# Cannon_V2.net
KiCad netlist of a schematic drawn in Altium Designer
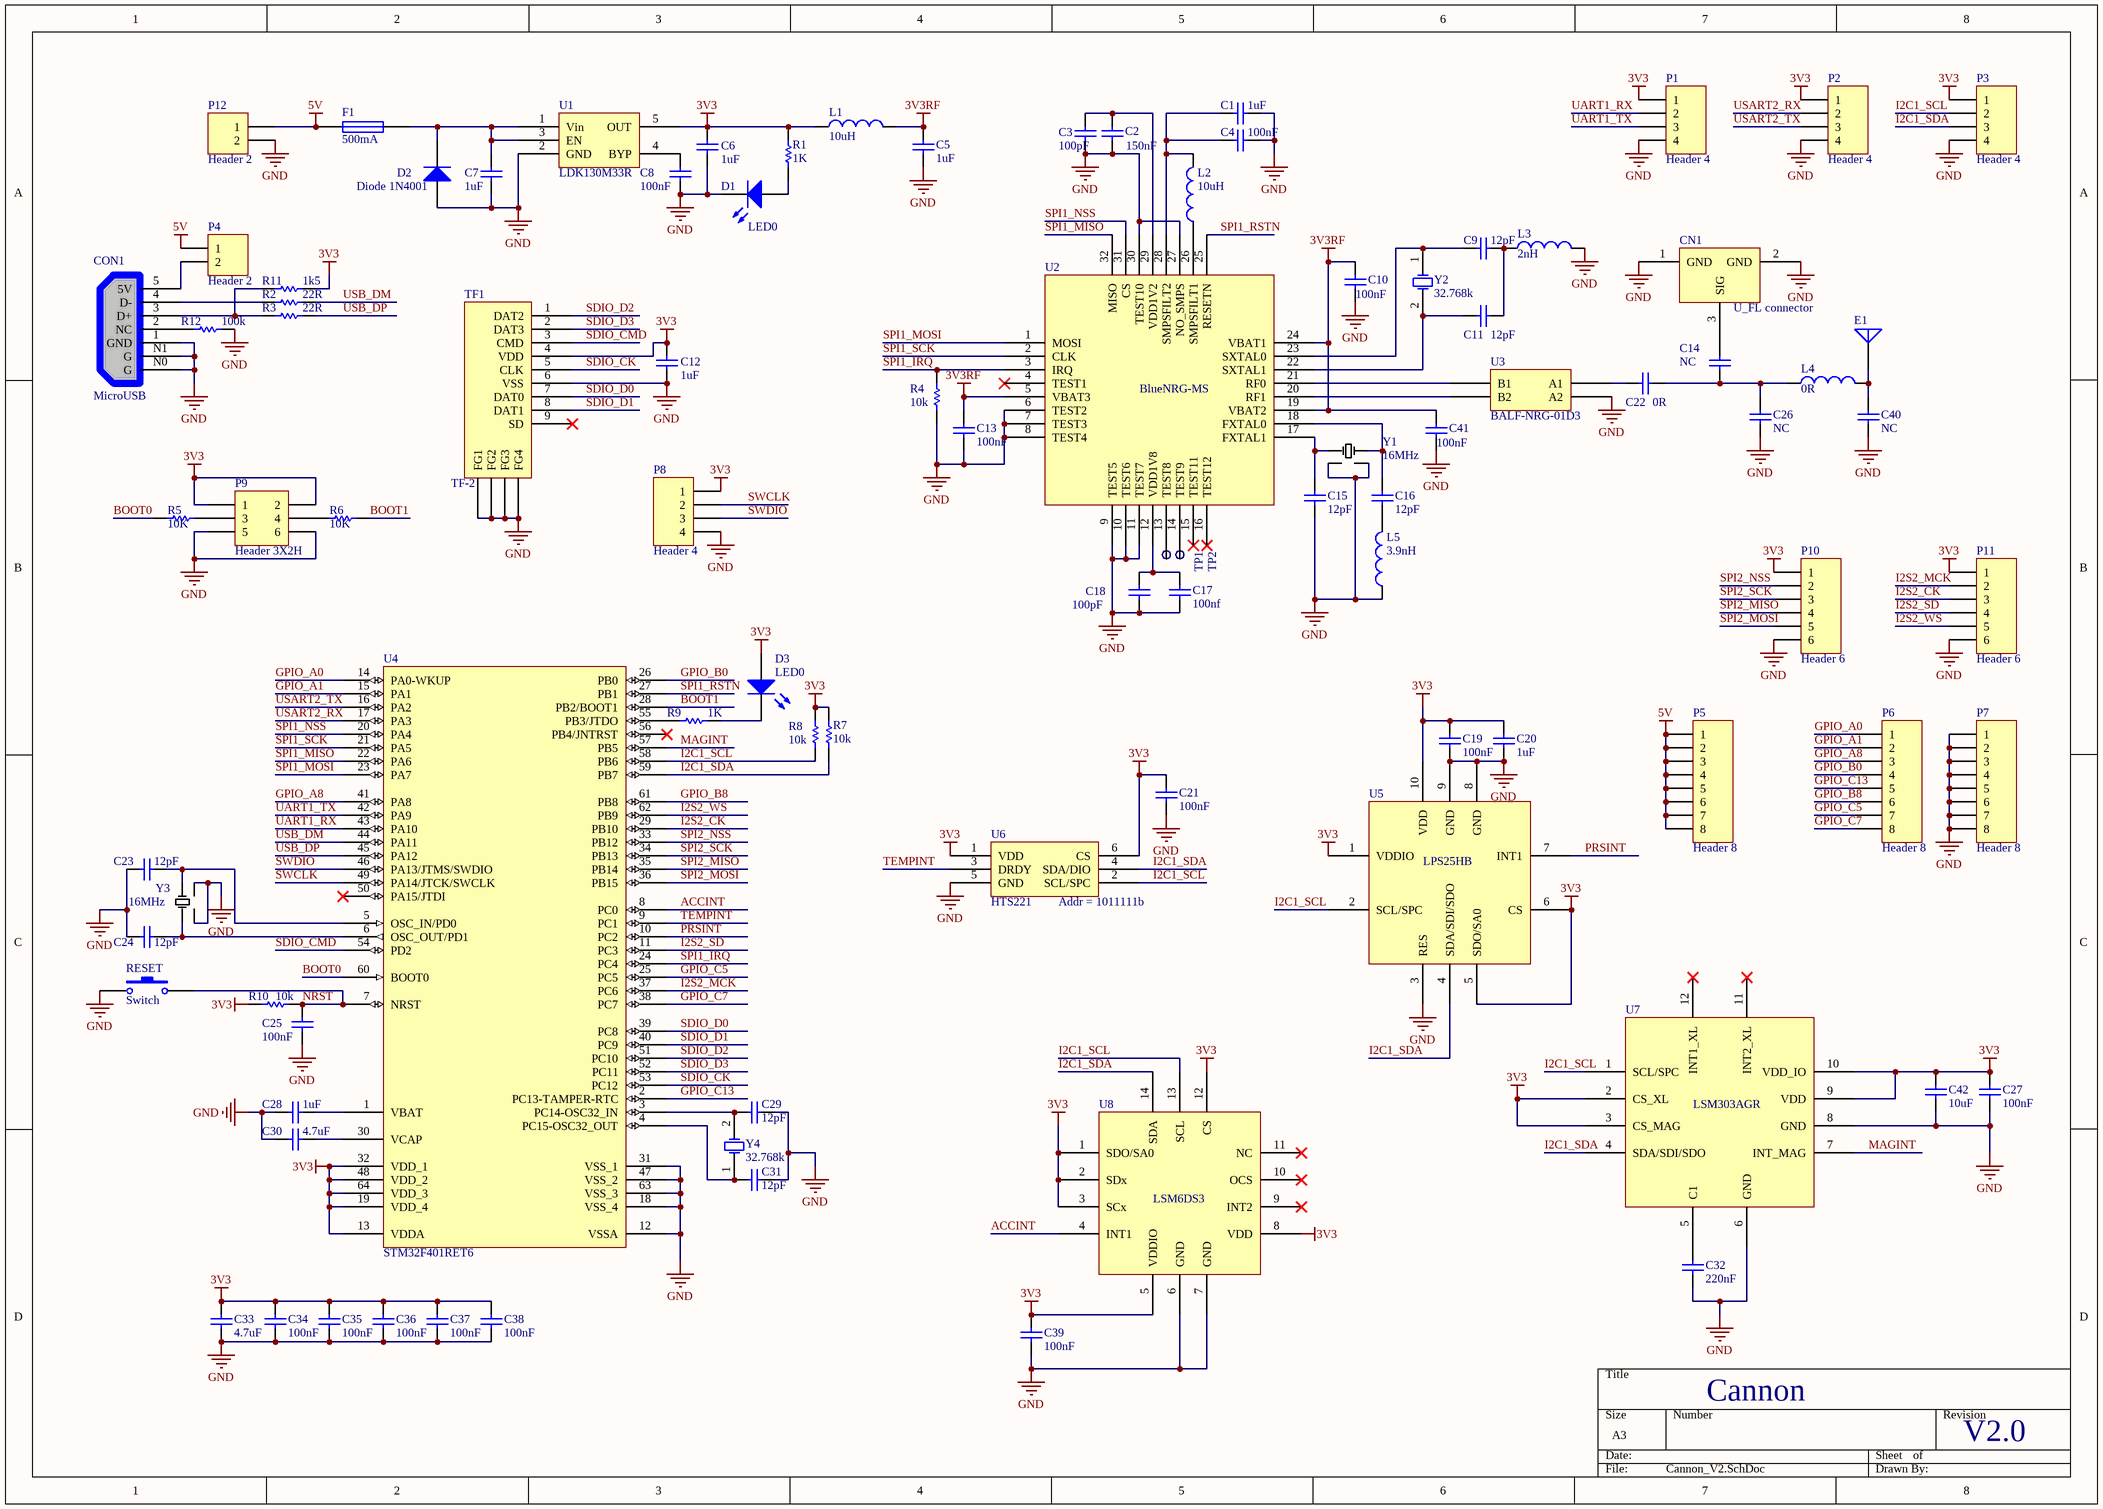
[diagram p0: Cannon_V2.SchDoc]

(export (version "E")
  (design (tool "Eeschema 10.0.6"))
  (components
    (comp (ref "C1")
      (value "1uF")
      (footprint "CAPC1608X06L")
      (description "Capacitor")
      (fields (field (name "PUBLISHER") "Altium Limited"))
      (libsource (lib "Miscellaneous Devices") (part "Cap"))
    )
    (comp (ref "C2")
      (value "150nF")
      (footprint "CAPC1005X04L")
      (description "Capacitor")
      (fields (field (name "PUBLISHER") "Altium Limited"))
      (libsource (lib "Miscellaneous Devices") (part "Cap"))
    )
    (comp (ref "C3")
      (value "100pF")
      (footprint "CAPC1005X04L")
      (description "Capacitor")
      (fields (field (name "PUBLISHER") "Altium Limited"))
      (libsource (lib "Miscellaneous Devices") (part "Cap"))
    )
    (comp (ref "C4")
      (value "100nF")
      (footprint "CAPC1005X04L")
      (description "Capacitor")
      (fields (field (name "PUBLISHER") "Altium Limited"))
      (libsource (lib "Miscellaneous Devices") (part "Cap"))
    )
    (comp (ref "C5")
      (value "1uF")
      (footprint "CAPC1608X06L")
      (description "Capacitor")
      (fields (field (name "PUBLISHER") "Altium Limited"))
      (libsource (lib "Miscellaneous Devices") (part "Cap"))
    )
    (comp (ref "C6")
      (value "1uF")
      (footprint "CAPC1608X06L")
      (description "Capacitor")
      (fields (field (name "PUBLISHER") "Altium Limited"))
      (libsource (lib "Miscellaneous Devices") (part "Cap"))
    )
    (comp (ref "C7")
      (value "1uF")
      (footprint "CAPC1608X06L")
      (description "Capacitor")
      (fields (field (name "PUBLISHER") "Altium Limited"))
      (libsource (lib "Miscellaneous Devices") (part "Cap"))
    )
    (comp (ref "C8")
      (value "100nF")
      (footprint "CAPC1005X04L")
      (description "Capacitor")
      (fields (field (name "PUBLISHER") "Altium Limited"))
      (libsource (lib "Miscellaneous Devices") (part "Cap"))
    )
    (comp (ref "C9")
      (value "12pF")
      (footprint "CAPC1005X04L")
      (description "Capacitor")
      (fields (field (name "PUBLISHER") "Altium Limited"))
      (libsource (lib "Miscellaneous Devices") (part "Cap"))
    )
    (comp (ref "C10")
      (value "100nF")
      (footprint "CAPC1005X04L")
      (description "Capacitor")
      (fields (field (name "PUBLISHER") "Altium Limited"))
      (libsource (lib "Miscellaneous Devices") (part "Cap"))
    )
    (comp (ref "C11")
      (value "12pF")
      (footprint "CAPC1005X04L")
      (description "Capacitor")
      (fields (field (name "PUBLISHER") "Altium Limited"))
      (libsource (lib "Miscellaneous Devices") (part "Cap"))
    )
    (comp (ref "C12")
      (value "1uF")
      (footprint "CAPC1608X06L")
      (description "Capacitor")
      (fields (field (name "PUBLISHER") "Altium Limited"))
      (libsource (lib "Miscellaneous Devices") (part "Cap"))
    )
    (comp (ref "C13")
      (value "100nF")
      (footprint "CAPC1005X04L")
      (description "Capacitor")
      (fields (field (name "PUBLISHER") "Altium Limited"))
      (libsource (lib "Miscellaneous Devices") (part "Cap"))
    )
    (comp (ref "C14")
      (value "NC")
      (footprint "CAPC1005X04L")
      (description "Capacitor")
      (fields (field (name "PUBLISHER") "Altium Limited"))
      (libsource (lib "Miscellaneous Devices") (part "Cap"))
    )
    (comp (ref "C15")
      (value "12pF")
      (footprint "CAPC1005X04L")
      (fields (field (name "PUBLISHER") "Altium Limited"))
      (libsource (lib "Miscellaneous Devices") (part "Cap Semi"))
    )
    (comp (ref "C16")
      (value "12pF")
      (footprint "CAPC1005X04L")
      (fields (field (name "PUBLISHER") "Altium Limited"))
      (libsource (lib "Miscellaneous Devices") (part "Cap Semi"))
    )
    (comp (ref "C17")
      (value "100nf")
      (footprint "CAPC1005X04L")
      (description "Capacitor")
      (fields (field (name "PUBLISHER") "Altium Limited"))
      (libsource (lib "Miscellaneous Devices") (part "Cap"))
    )
    (comp (ref "C18")
      (value "100pF")
      (footprint "CAPC1005X04L")
      (description "Capacitor")
      (fields (field (name "PUBLISHER") "Altium Limited"))
      (libsource (lib "Miscellaneous Devices") (part "Cap"))
    )
    (comp (ref "C19")
      (value "100nF")
      (footprint "CAPC1005X04L")
      (description "Capacitor")
      (fields (field (name "PUBLISHER") "Altium Limited"))
      (libsource (lib "Miscellaneous Devices") (part "Cap"))
    )
    (comp (ref "C20")
      (value "1uF")
      (footprint "CAPC1608X06L")
      (description "Capacitor")
      (fields (field (name "PUBLISHER") "Altium Limited"))
      (libsource (lib "Miscellaneous Devices") (part "Cap"))
    )
    (comp (ref "C21")
      (value "100nF")
      (footprint "CAPC1005X04L")
      (description "Capacitor")
      (fields (field (name "PUBLISHER") "Altium Limited"))
      (libsource (lib "Miscellaneous Devices") (part "Cap"))
    )
    (comp (ref "C22")
      (value "0R")
      (footprint "CAPC1005X04L")
      (description "Capacitor")
      (fields (field (name "PUBLISHER") "Altium Limited"))
      (libsource (lib "Miscellaneous Devices") (part "Cap"))
    )
    (comp (ref "C23")
      (value "12pF")
      (footprint "CAPC1005X04L")
      (description "Capacitor")
      (fields (field (name "PUBLISHER") "Altium Limited"))
      (libsource (lib "Miscellaneous Devices") (part "Cap"))
    )
    (comp (ref "C24")
      (value "12pF")
      (footprint "CAPC1005X04L")
      (description "Capacitor")
      (fields (field (name "PUBLISHER") "Altium Limited"))
      (libsource (lib "Miscellaneous Devices") (part "Cap"))
    )
    (comp (ref "C25")
      (value "100nF")
      (footprint "CAPC1005X04L")
      (description "Capacitor")
      (fields (field (name "PUBLISHER") "Altium Limited"))
      (libsource (lib "Miscellaneous Devices") (part "Cap"))
    )
    (comp (ref "C26")
      (value "NC")
      (footprint "CAPC1005X04L")
      (description "Capacitor")
      (fields (field (name "PUBLISHER") "Altium Limited"))
      (libsource (lib "Miscellaneous Devices") (part "Cap"))
    )
    (comp (ref "C27")
      (value "100nF")
      (footprint "CAPC1005X04L")
      (description "Capacitor")
      (fields (field (name "PUBLISHER") "Altium Limited"))
      (libsource (lib "Miscellaneous Devices") (part "Cap"))
    )
    (comp (ref "C28")
      (value "1uF")
      (footprint "CAPC1608X06L")
      (description "Capacitor")
      (fields (field (name "PUBLISHER") "Altium Limited"))
      (libsource (lib "Miscellaneous Devices") (part "Cap"))
    )
    (comp (ref "C29")
      (value "12pF")
      (footprint "CAPC1005X04L")
      (description "Capacitor")
      (fields (field (name "PUBLISHER") "Altium Limited"))
      (libsource (lib "Miscellaneous Devices") (part "Cap"))
    )
    (comp (ref "C30")
      (value "4.7uF")
      (footprint "CAPC1608X06L")
      (description "Capacitor")
      (fields (field (name "PUBLISHER") "Altium Limited"))
      (libsource (lib "Miscellaneous Devices") (part "Cap"))
    )
    (comp (ref "C31")
      (value "12pF")
      (footprint "CAPC1005X04L")
      (description "Capacitor")
      (fields (field (name "PUBLISHER") "Altium Limited"))
      (libsource (lib "Miscellaneous Devices") (part "Cap"))
    )
    (comp (ref "C32")
      (value "220nF")
      (footprint "CAPC1005X04L")
      (description "Capacitor")
      (fields (field (name "PUBLISHER") "Altium Limited"))
      (libsource (lib "Miscellaneous Devices") (part "Cap"))
    )
    (comp (ref "C33")
      (value "4.7uF")
      (footprint "CAPC1608X06L")
      (description "Capacitor")
      (fields (field (name "PUBLISHER") "Altium Limited"))
      (libsource (lib "Miscellaneous Devices") (part "Cap"))
    )
    (comp (ref "C34")
      (value "100nF")
      (footprint "CAPC1005X04L")
      (description "Capacitor")
      (fields (field (name "PUBLISHER") "Altium Limited"))
      (libsource (lib "Miscellaneous Devices") (part "Cap"))
    )
    (comp (ref "C35")
      (value "100nF")
      (footprint "CAPC1005X04L")
      (description "Capacitor")
      (fields (field (name "PUBLISHER") "Altium Limited"))
      (libsource (lib "Miscellaneous Devices") (part "Cap"))
    )
    (comp (ref "C36")
      (value "100nF")
      (footprint "CAPC1005X04L")
      (description "Capacitor")
      (fields (field (name "PUBLISHER") "Altium Limited"))
      (libsource (lib "Miscellaneous Devices") (part "Cap"))
    )
    (comp (ref "C37")
      (value "100nF")
      (footprint "CAPC1005X04L")
      (description "Capacitor")
      (fields (field (name "PUBLISHER") "Altium Limited"))
      (libsource (lib "Miscellaneous Devices") (part "Cap"))
    )
    (comp (ref "C38")
      (value "100nF")
      (footprint "CAPC1005X04L")
      (description "Capacitor")
      (fields (field (name "PUBLISHER") "Altium Limited"))
      (libsource (lib "Miscellaneous Devices") (part "Cap"))
    )
    (comp (ref "C39")
      (value "100nF")
      (footprint "CAPC1005X04L")
      (description "Capacitor")
      (fields (field (name "PUBLISHER") "Altium Limited"))
      (libsource (lib "Miscellaneous Devices") (part "Cap"))
    )
    (comp (ref "C40")
      (value "NC")
      (footprint "CAPC1005X04L")
      (description "Capacitor")
      (fields (field (name "PUBLISHER") "Altium Limited"))
      (libsource (lib "Miscellaneous Devices") (part "Cap"))
    )
    (comp (ref "C41")
      (value "100nF")
      (footprint "CAPC1005X04L")
      (description "Capacitor")
      (fields (field (name "PUBLISHER") "Altium Limited"))
      (libsource (lib "Miscellaneous Devices") (part "Cap"))
    )
    (comp (ref "C42")
      (value "10uF")
      (footprint "CAPC1608X06L")
      (description "Capacitor")
      (fields (field (name "PUBLISHER") "Altium Limited"))
      (libsource (lib "Miscellaneous Devices") (part "Cap"))
    )
    (comp (ref "CN1")
      (value "U_FL connector")
      (footprint "UFL")
      (libsource (lib "STC") (part "U_FL connector"))
    )
    (comp (ref "CON1")
      (value "MicroUSB")
      (footprint "Micro_USB")
      (libsource (lib "mylib") (part "MicroUSB_A"))
    )
    (comp (ref "D1")
      (value "LED0")
      (footprint "INDC1608L")
      (description "Typical INFRARED GaAs LED")
      (fields (field (name "PUBLISHER") "Altium Limited"))
      (libsource (lib "Miscellaneous Devices") (part "LED0"))
    )
    (comp (ref "D2")
      (value "Diode 1N4001")
      (footprint "SOD323")
      (description "1 Amp General Purpose Rectifier")
      (fields (field (name "PUBLISHER") "Altium Limited"))
      (libsource (lib "Miscellaneous Devices") (part "Diode 1N4001"))
    )
    (comp (ref "D3")
      (value "LED0")
      (footprint "INDC1608L")
      (description "Typical INFRARED GaAs LED")
      (fields (field (name "PUBLISHER") "Altium Limited"))
      (libsource (lib "Miscellaneous Devices") (part "LED0"))
    )
    (comp (ref "E1")
      (value "Antenna")
      (footprint "INDM9621X21N")
      (description "Generic Antenna")
      (fields (field (name "PUBLISHER") "Altium Limited"))
      (libsource (lib "Miscellaneous Devices") (part "Antenna"))
    )
    (comp (ref "F1")
      (value "500mA")
      (footprint "6-0805_N")
      (description "Fuse")
      (fields (field (name "PUBLISHER") "Altium Limited"))
      (libsource (lib "Miscellaneous Devices") (part "Fuse 1"))
    )
    (comp (ref "L1")
      (value "10uH")
      (footprint "INDC1608X06L")
      (description "Inductor")
      (fields (field (name "PUBLISHER") "Altium Limited"))
      (libsource (lib "Miscellaneous Devices") (part "Inductor"))
    )
    (comp (ref "L2")
      (value "10uH")
      (footprint "INDC1608X06L")
      (description "Inductor")
      (fields (field (name "PUBLISHER") "Altium Limited"))
      (libsource (lib "Miscellaneous Devices") (part "Inductor"))
    )
    (comp (ref "L3")
      (value "2nH")
      (footprint "INDC1005X04L")
      (description "Inductor")
      (fields (field (name "PUBLISHER") "Altium Limited"))
      (libsource (lib "Miscellaneous Devices") (part "Inductor"))
    )
    (comp (ref "L4")
      (value "0R")
      (footprint "INDC1005X04L")
      (description "Inductor")
      (fields (field (name "PUBLISHER") "Altium Limited"))
      (libsource (lib "Miscellaneous Devices") (part "Inductor"))
    )
    (comp (ref "L5")
      (value "3.9nH")
      (footprint "INDC1005X04L")
      (description "Inductor")
      (fields (field (name "PUBLISHER") "Altium Limited"))
      (libsource (lib "Miscellaneous Devices") (part "Inductor"))
    )
    (comp (ref "P1")
      (value "Header 4")
      (footprint "HDR1X4")
      (description "Header, 4-Pin")
      (fields (field (name "PUBLISHER") "Altium Limited"))
      (libsource (lib "Miscellaneous Connectors") (part "Header 4"))
    )
    (comp (ref "P2")
      (value "Header 4")
      (footprint "HDR1X4")
      (description "Header, 4-Pin")
      (fields (field (name "PUBLISHER") "Altium Limited"))
      (libsource (lib "Miscellaneous Connectors") (part "Header 4"))
    )
    (comp (ref "P3")
      (value "Header 4")
      (footprint "HDR1X4")
      (description "Header, 4-Pin")
      (fields (field (name "PUBLISHER") "Altium Limited"))
      (libsource (lib "Miscellaneous Connectors") (part "Header 4"))
    )
    (comp (ref "P4")
      (value "Header 2")
      (footprint "HDR1X2")
      (description "Header, 2-Pin")
      (fields (field (name "PUBLISHER") "Altium Limited"))
      (libsource (lib "") (part "Header 2_1"))
    )
    (comp (ref "P5")
      (value "Header 8")
      (footprint "HDR1X8")
      (description "Header, 8-Pin")
      (fields (field (name "PUBLISHER") "Altium Limited"))
      (libsource (lib "Miscellaneous Connectors") (part "Header 8"))
    )
    (comp (ref "P6")
      (value "Header 8")
      (footprint "HDR1X8")
      (description "Header, 8-Pin")
      (fields (field (name "PUBLISHER") "Altium Limited"))
      (libsource (lib "Miscellaneous Connectors") (part "Header 8"))
    )
    (comp (ref "P7")
      (value "Header 8")
      (footprint "HDR1X8")
      (description "Header, 8-Pin")
      (fields (field (name "PUBLISHER") "Altium Limited"))
      (libsource (lib "Miscellaneous Connectors") (part "Header 8"))
    )
    (comp (ref "P8")
      (value "Header 4")
      (footprint "HDR1X4")
      (description "Header, 4-Pin")
      (fields (field (name "PUBLISHER") "Altium Limited"))
      (libsource (lib "") (part "Header 4_1"))
    )
    (comp (ref "P9")
      (value "Header 3X2H")
      (footprint "HDR2X3")
      (description "Header, 3-Pin, Dual row, Right Angle")
      (fields (field (name "PUBLISHER") "Altium Limited"))
      (libsource (lib "Miscellaneous Connectors") (part "Header 3X2H"))
    )
    (comp (ref "P10")
      (value "Header 6")
      (footprint "HDR1X6")
      (description "Header, 6-Pin")
      (fields (field (name "PUBLISHER") "Altium Limited"))
      (libsource (lib "Miscellaneous Connectors") (part "Header 6"))
    )
    (comp (ref "P11")
      (value "Header 6")
      (footprint "HDR1X6")
      (description "Header, 6-Pin")
      (fields (field (name "PUBLISHER") "Altium Limited"))
      (libsource (lib "Miscellaneous Connectors") (part "Header 6"))
    )
    (comp (ref "P12")
      (value "Header 2")
      (footprint "SIP_2")
      (description "Header, 2-Pin")
      (fields (field (name "PUBLISHER") "Altium Limited"))
      (libsource (lib "Miscellaneous Connectors") (part "Header 2"))
    )
    (comp (ref "R1")
      (value "1K")
      (footprint "INDC1005X04L")
      (description "Resistor")
      (fields (field (name "PUBLISHER") "Altium Limited"))
      (libsource (lib "Miscellaneous Devices") (part "Res1"))
    )
    (comp (ref "R2")
      (value "22R")
      (footprint "INDC1005X04L")
      (description "Resistor")
      (fields (field (name "PUBLISHER") "Altium Limited"))
      (libsource (lib "Miscellaneous Devices") (part "Res1"))
    )
    (comp (ref "R3")
      (value "22R")
      (footprint "INDC1005X04L")
      (description "Resistor")
      (fields (field (name "PUBLISHER") "Altium Limited"))
      (libsource (lib "Miscellaneous Devices") (part "Res1"))
    )
    (comp (ref "R4")
      (value "10k")
      (footprint "INDC1005X04L")
      (description "Resistor")
      (fields (field (name "PUBLISHER") "Altium Limited"))
      (libsource (lib "Miscellaneous Devices") (part "Res1"))
    )
    (comp (ref "R5")
      (value "10K")
      (footprint "INDC1005X04L")
      (description "Resistor")
      (fields (field (name "PUBLISHER") "Altium Limited"))
      (libsource (lib "Miscellaneous Devices") (part "Res1"))
    )
    (comp (ref "R6")
      (value "10K")
      (footprint "INDC1005X04L")
      (description "Resistor")
      (fields (field (name "PUBLISHER") "Altium Limited"))
      (libsource (lib "Miscellaneous Devices") (part "Res1"))
    )
    (comp (ref "R7")
      (value "10k")
      (footprint "INDC1005X04L")
      (description "Resistor")
      (fields (field (name "PUBLISHER") "Altium Limited"))
      (libsource (lib "Miscellaneous Devices") (part "Res1"))
    )
    (comp (ref "R8")
      (value "10k")
      (footprint "INDC1005X04L")
      (description "Resistor")
      (fields (field (name "PUBLISHER") "Altium Limited"))
      (libsource (lib "Miscellaneous Devices") (part "Res1"))
    )
    (comp (ref "R9")
      (value "1K")
      (footprint "INDC1005X04L")
      (description "Resistor")
      (fields (field (name "PUBLISHER") "Altium Limited"))
      (libsource (lib "Miscellaneous Devices") (part "Res1"))
    )
    (comp (ref "R10")
      (value "10k")
      (footprint "INDC1005X04L")
      (description "Resistor")
      (fields (field (name "PUBLISHER") "Altium Limited"))
      (libsource (lib "Miscellaneous Devices") (part "Res1"))
    )
    (comp (ref "R11")
      (value "1k5")
      (footprint "INDC1005X04L")
      (description "Resistor")
      (fields (field (name "PUBLISHER") "Altium Limited"))
      (libsource (lib "Miscellaneous Devices") (part "Res1"))
    )
    (comp (ref "R12")
      (value "100k")
      (footprint "INDC1005X04L")
      (description "Resistor")
      (fields (field (name "PUBLISHER") "Altium Limited"))
      (libsource (lib "Miscellaneous Devices") (part "Res1"))
    )
    (comp (ref "RESET")
      (value "Switch")
      (footprint "SW_THT_4x4x1.5")
      (description "Micro miniature pushbutton surface Switch")
      (fields (field (name "PART NUMBER") "SW THT 6x6x5") (field (name "MANUFACTURER") "Würth"))
      (libsource (lib "Electromechanical") (part "Switch"))
    )
    (comp (ref "TF1") (value "TF-2") (footprint "TF-2") (libsource (lib "STC") (part "TF-2")))
    (comp (ref "TP1") (value "TP") (footprint "TP-1x1") (libsource (lib "STC") (part "TP")))
    (comp (ref "TP2") (value "TP") (footprint "TP-1x1") (libsource (lib "STC") (part "TP")))
    (comp (ref "U1") (value "LDK130M33R") (footprint "SOT23-5L") (libsource (lib "STC") (part "LDK130M33R")))
    (comp (ref "U2") (value "BlueNRG-MS") (footprint "QFN32") (libsource (lib "STC") (part "BlueNRG-MS")))
    (comp (ref "U3")
      (value "BALF-NRG-01D3")
      (footprint "BALF-PK")
      (libsource (lib "STC") (part "BALF-NRG-01D3"))
    )
    (comp (ref "U4")
      (value "STM32F401RET6")
      (footprint "LQFP64_N")
      (description "STM32 ARM-based 32-bit MCU with 256 Kbytes Flash, 64-pin LQFP, Industrial Temperature")
      (fields (field (name "PUBLISHER") "Altium Limited"))
      (libsource (lib "STC") (part "STM32F401RET6"))
    )
    (comp (ref "U5") (value "LPS25HB") (footprint "HLGA-10L") (libsource (lib "STC") (part "LPS25H")))
    (comp (ref "U6") (value "HTS221") (footprint "HLGA-6L") (libsource (lib "STC") (part "HTS221")))
    (comp (ref "U7") (value "LSM303AGR") (footprint "LGA12") (libsource (lib "STC") (part "LSM303AGR")))
    (comp (ref "U8") (value "LSM6DS3") (footprint "LGA-14L") (libsource (lib "STC") (part "LSM6DS3")))
    (comp (ref "Y1") (value "16MHz") (footprint "3225") (libsource (lib "mylib") (part "3225")))
    (comp (ref "Y2")
      (value "32.768k")
      (footprint "XTAL_3215")
      (description "Crystal Oscillator")
      (fields (field (name "PUBLISHER") "Altium Limited"))
      (libsource (lib "Miscellaneous Devices") (part "XTAL"))
    )
    (comp (ref "Y3") (value "16MHz") (footprint "3225") (libsource (lib "mylib") (part "3225")))
    (comp (ref "Y4")
      (value "32.768k")
      (footprint "XTAL_3215")
      (description "Crystal Oscillator")
      (fields (field (name "PUBLISHER") "Altium Limited"))
      (libsource (lib "Miscellaneous Devices") (part "XTAL"))
    )
  )
  (nets
    (net (code "1") (name "/ACCINT") (class "Default")
      (node (ref "U4") (pin "8") (pinfunction "PC0_8") (pintype "bidirectional"))
      (node (ref "U8") (pin "4") (pinfunction "INT1_4") (pintype "passive"))
    )
    (net (code "2") (name "/BOOT0") (class "Default")
      (node (ref "R5") (pin "1") (pinfunction "1_1") (pintype "passive"))
      (node (ref "U4") (pin "60") (pinfunction "BOOT0_60") (pintype "input"))
    )
    (net (code "3") (name "/BOOT1") (class "Default")
      (node (ref "R6") (pin "2") (pinfunction "2_2") (pintype "passive"))
      (node (ref "U4") (pin "28") (pinfunction "PB2/BOOT1_28") (pintype "bidirectional"))
    )
    (net (code "4") (name "/GPIO_A0") (class "Default")
      (node (ref "P6") (pin "1") (pinfunction "1_1") (pintype "passive"))
      (node (ref "U4") (pin "14") (pinfunction "PA0-WKUP_14") (pintype "bidirectional"))
    )
    (net (code "5") (name "/GPIO_A1") (class "Default")
      (node (ref "P6") (pin "2") (pinfunction "2_2") (pintype "passive"))
      (node (ref "U4") (pin "15") (pinfunction "PA1_15") (pintype "bidirectional"))
    )
    (net (code "6") (name "/GPIO_A8") (class "Default")
      (node (ref "P6") (pin "3") (pinfunction "3_3") (pintype "passive"))
      (node (ref "U4") (pin "41") (pinfunction "PA8_41") (pintype "bidirectional"))
    )
    (net (code "7") (name "/GPIO_B0") (class "Default")
      (node (ref "P6") (pin "4") (pinfunction "4_4") (pintype "passive"))
      (node (ref "U4") (pin "26") (pinfunction "PB0_26") (pintype "bidirectional"))
    )
    (net (code "8") (name "/GPIO_B8") (class "Default")
      (node (ref "P6") (pin "6") (pinfunction "6_6") (pintype "passive"))
      (node (ref "U4") (pin "61") (pinfunction "PB8_61") (pintype "bidirectional"))
    )
    (net (code "9") (name "/GPIO_C5") (class "Default")
      (node (ref "P6") (pin "7") (pinfunction "7_7") (pintype "passive"))
      (node (ref "U4") (pin "25") (pinfunction "PC5_25") (pintype "bidirectional"))
    )
    (net (code "10") (name "/GPIO_C7") (class "Default")
      (node (ref "P6") (pin "8") (pinfunction "8_8") (pintype "passive"))
      (node (ref "U4") (pin "38") (pinfunction "PC7_38") (pintype "bidirectional"))
    )
    (net (code "11") (name "/GPIO_C13") (class "Default")
      (node (ref "P6") (pin "5") (pinfunction "5_5") (pintype "passive"))
      (node (ref "U4") (pin "2") (pinfunction "PC13-TAMPER-RTC_2") (pintype "bidirectional"))
    )
    (net (code "12") (name "/I2C1_SCL") (class "Default")
      (node (ref "P3") (pin "2") (pinfunction "2_2") (pintype "passive"))
      (node (ref "R8") (pin "2") (pinfunction "2_2") (pintype "passive"))
      (node (ref "U4") (pin "58") (pinfunction "PB6_58") (pintype "bidirectional"))
      (node (ref "U5") (pin "2") (pinfunction "SCL/SPC_2") (pintype "passive"))
      (node (ref "U6") (pin "2") (pinfunction "SCL/SPC_2") (pintype "passive"))
      (node (ref "U7") (pin "1") (pinfunction "SCL/SPC_1") (pintype "passive"))
      (node (ref "U8") (pin "13") (pinfunction "SCL_13") (pintype "passive"))
    )
    (net (code "13") (name "/I2C1_SDA") (class "Default")
      (node (ref "P3") (pin "3") (pinfunction "3_3") (pintype "passive"))
      (node (ref "R7") (pin "2") (pinfunction "2_2") (pintype "passive"))
      (node (ref "U4") (pin "59") (pinfunction "PB7_59") (pintype "bidirectional"))
      (node (ref "U5") (pin "4") (pinfunction "SDA/SDI/SDO_4") (pintype "passive"))
      (node (ref "U6") (pin "4") (pinfunction "SDA/DIO_4") (pintype "passive"))
      (node (ref "U7") (pin "4") (pinfunction "SDA/SDI/SDO_4") (pintype "passive"))
      (node (ref "U8") (pin "14") (pinfunction "SDA_14") (pintype "passive"))
    )
    (net (code "14") (name "/I2S2_CK") (class "Default")
      (node (ref "P11") (pin "3") (pinfunction "3_3") (pintype "passive"))
      (node (ref "U4") (pin "29") (pinfunction "PB10_29") (pintype "bidirectional"))
    )
    (net (code "15") (name "/I2S2_MCK") (class "Default")
      (node (ref "P11") (pin "2") (pinfunction "2_2") (pintype "passive"))
      (node (ref "U4") (pin "37") (pinfunction "PC6_37") (pintype "bidirectional"))
    )
    (net (code "16") (name "/I2S2_SD") (class "Default")
      (node (ref "P11") (pin "4") (pinfunction "4_4") (pintype "passive"))
      (node (ref "U4") (pin "11") (pinfunction "PC3_11") (pintype "bidirectional"))
    )
    (net (code "17") (name "/I2S2_WS") (class "Default")
      (node (ref "P11") (pin "5") (pinfunction "5_5") (pintype "passive"))
      (node (ref "U4") (pin "62") (pinfunction "PB9_62") (pintype "bidirectional"))
    )
    (net (code "18") (name "/MAGINT") (class "Default")
      (node (ref "U4") (pin "57") (pinfunction "PB5_57") (pintype "bidirectional"))
      (node (ref "U7") (pin "7") (pinfunction "INT_MAG_7") (pintype "passive"))
    )
    (net (code "19") (name "/NRST") (class "Default")
      (node (ref "C25") (pin "2") (pinfunction "2_2") (pintype "passive"))
      (node (ref "R10") (pin "1") (pinfunction "1_1") (pintype "passive"))
      (node (ref "RESET") (pin "2") (pinfunction "2_2") (pintype "passive"))
      (node (ref "U4") (pin "7") (pinfunction "NRST_7") (pintype "bidirectional"))
    )
    (net (code "20") (name "/PRSINT") (class "Default")
      (node (ref "U4") (pin "10") (pinfunction "PC2_10") (pintype "bidirectional"))
      (node (ref "U5") (pin "7") (pinfunction "INT1_7") (pintype "passive"))
    )
    (net (code "21") (name "/SDIO_CK") (class "Default")
      (node (ref "TF1") (pin "5") (pinfunction "CLK_5") (pintype "passive"))
      (node (ref "U4") (pin "53") (pinfunction "PC12_53") (pintype "bidirectional"))
    )
    (net (code "22") (name "/SDIO_CMD") (class "Default")
      (node (ref "TF1") (pin "3") (pinfunction "CMD_3") (pintype "passive"))
      (node (ref "U4") (pin "54") (pinfunction "PD2_54") (pintype "bidirectional"))
    )
    (net (code "23") (name "/SDIO_D0") (class "Default")
      (node (ref "TF1") (pin "7") (pinfunction "DAT0_7") (pintype "passive"))
      (node (ref "U4") (pin "39") (pinfunction "PC8_39") (pintype "bidirectional"))
    )
    (net (code "24") (name "/SDIO_D1") (class "Default")
      (node (ref "TF1") (pin "8") (pinfunction "DAT1_8") (pintype "passive"))
      (node (ref "U4") (pin "40") (pinfunction "PC9_40") (pintype "bidirectional"))
    )
    (net (code "25") (name "/SDIO_D2") (class "Default")
      (node (ref "TF1") (pin "1") (pinfunction "DAT2_1") (pintype "passive"))
      (node (ref "U4") (pin "51") (pinfunction "PC10_51") (pintype "bidirectional"))
    )
    (net (code "26") (name "/SDIO_D3") (class "Default")
      (node (ref "TF1") (pin "2") (pinfunction "DAT3_2") (pintype "passive"))
      (node (ref "U4") (pin "52") (pinfunction "PC11_52") (pintype "bidirectional"))
    )
    (net (code "27") (name "/SPI1_IRQ") (class "Default")
      (node (ref "R4") (pin "1") (pinfunction "1_1") (pintype "passive"))
      (node (ref "U2") (pin "3") (pinfunction "IRQ_3") (pintype "passive"))
      (node (ref "U4") (pin "24") (pinfunction "PC4_24") (pintype "bidirectional"))
    )
    (net (code "28") (name "/SPI1_MISO") (class "Default")
      (node (ref "U2") (pin "32") (pinfunction "MISO_32") (pintype "passive"))
      (node (ref "U4") (pin "22") (pinfunction "PA6_22") (pintype "bidirectional"))
    )
    (net (code "29") (name "/SPI1_MOSI") (class "Default")
      (node (ref "U2") (pin "1") (pinfunction "MOSI_1") (pintype "passive"))
      (node (ref "U4") (pin "23") (pinfunction "PA7_23") (pintype "bidirectional"))
    )
    (net (code "30") (name "/SPI1_NSS") (class "Default")
      (node (ref "U2") (pin "31") (pinfunction "CS_31") (pintype "passive"))
      (node (ref "U4") (pin "20") (pinfunction "PA4_20") (pintype "bidirectional"))
    )
    (net (code "31") (name "/SPI1_RSTN") (class "Default")
      (node (ref "U2") (pin "25") (pinfunction "RESETN_25") (pintype "passive"))
      (node (ref "U4") (pin "27") (pinfunction "PB1_27") (pintype "bidirectional"))
    )
    (net (code "32") (name "/SPI1_SCK") (class "Default")
      (node (ref "U2") (pin "2") (pinfunction "CLK_2") (pintype "passive"))
      (node (ref "U4") (pin "21") (pinfunction "PA5_21") (pintype "bidirectional"))
    )
    (net (code "33") (name "/SPI2_MISO") (class "Default")
      (node (ref "P10") (pin "4") (pinfunction "4_4") (pintype "passive"))
      (node (ref "U4") (pin "35") (pinfunction "PB14_35") (pintype "bidirectional"))
    )
    (net (code "34") (name "/SPI2_MOSI") (class "Default")
      (node (ref "P10") (pin "5") (pinfunction "5_5") (pintype "passive"))
      (node (ref "U4") (pin "36") (pinfunction "PB15_36") (pintype "bidirectional"))
    )
    (net (code "35") (name "/SPI2_NSS") (class "Default")
      (node (ref "P10") (pin "2") (pinfunction "2_2") (pintype "passive"))
      (node (ref "U4") (pin "33") (pinfunction "PB12_33") (pintype "bidirectional"))
    )
    (net (code "36") (name "/SPI2_SCK") (class "Default")
      (node (ref "P10") (pin "3") (pinfunction "3_3") (pintype "passive"))
      (node (ref "U4") (pin "34") (pinfunction "PB13_34") (pintype "bidirectional"))
    )
    (net (code "37") (name "/SWCLK") (class "Default")
      (node (ref "P8") (pin "2") (pinfunction "2_2") (pintype "passive"))
      (node (ref "U4") (pin "49") (pinfunction "PA14/JTCK/SWCLK_49") (pintype "bidirectional"))
    )
    (net (code "38") (name "/SWDIO") (class "Default")
      (node (ref "P8") (pin "3") (pinfunction "3_3") (pintype "passive"))
      (node (ref "U4") (pin "46") (pinfunction "PA13/JTMS/SWDIO_46") (pintype "bidirectional"))
    )
    (net (code "39") (name "/TEMPINT") (class "Default")
      (node (ref "U4") (pin "9") (pinfunction "PC1_9") (pintype "bidirectional"))
      (node (ref "U6") (pin "3") (pinfunction "DRDY_3") (pintype "passive"))
    )
    (net (code "40") (name "/UART1_RX") (class "Default")
      (node (ref "P1") (pin "2") (pinfunction "2_2") (pintype "passive"))
      (node (ref "U4") (pin "43") (pinfunction "PA10_43") (pintype "bidirectional"))
    )
    (net (code "41") (name "/UART1_TX") (class "Default")
      (node (ref "P1") (pin "3") (pinfunction "3_3") (pintype "passive"))
      (node (ref "U4") (pin "42") (pinfunction "PA9_42") (pintype "bidirectional"))
    )
    (net (code "42") (name "/USART2_RX") (class "Default")
      (node (ref "P2") (pin "2") (pinfunction "2_2") (pintype "passive"))
      (node (ref "U4") (pin "17") (pinfunction "PA3_17") (pintype "bidirectional"))
    )
    (net (code "43") (name "/USART2_TX") (class "Default")
      (node (ref "P2") (pin "3") (pinfunction "3_3") (pintype "passive"))
      (node (ref "U4") (pin "16") (pinfunction "PA2_16") (pintype "bidirectional"))
    )
    (net (code "44") (name "/USB_DM") (class "Default")
      (node (ref "R2") (pin "2") (pinfunction "2_2") (pintype "passive"))
      (node (ref "U4") (pin "44") (pinfunction "PA11_44") (pintype "bidirectional"))
    )
    (net (code "45") (name "/USB_DP") (class "Default")
      (node (ref "R3") (pin "2") (pinfunction "2_2") (pintype "passive"))
      (node (ref "U4") (pin "45") (pinfunction "PA12_45") (pintype "bidirectional"))
    )
    (net (code "46") (name "3V3") (class "Default")
      (node (ref "C12") (pin "2") (pinfunction "2_2") (pintype "passive"))
      (node (ref "C19") (pin "2") (pinfunction "2_2") (pintype "passive"))
      (node (ref "C20") (pin "1") (pinfunction "1_1") (pintype "passive"))
      (node (ref "C21") (pin "2") (pinfunction "2_2") (pintype "passive"))
      (node (ref "C27") (pin "1") (pinfunction "1_1") (pintype "passive"))
      (node (ref "C33") (pin "2") (pinfunction "2_2") (pintype "passive"))
      (node (ref "C34") (pin "1") (pinfunction "1_1") (pintype "passive"))
      (node (ref "C35") (pin "1") (pinfunction "1_1") (pintype "passive"))
      (node (ref "C36") (pin "1") (pinfunction "1_1") (pintype "passive"))
      (node (ref "C37") (pin "1") (pinfunction "1_1") (pintype "passive"))
      (node (ref "C38") (pin "1") (pinfunction "1_1") (pintype "passive"))
      (node (ref "C39") (pin "1") (pinfunction "1_1") (pintype "passive"))
      (node (ref "C42") (pin "1") (pinfunction "1_1") (pintype "passive"))
      (node (ref "C6") (pin "2") (pinfunction "2_2") (pintype "passive"))
      (node (ref "D3") (pin "2") (pinfunction "A_2") (pintype "passive"))
      (node (ref "L1") (pin "1") (pinfunction "1_1") (pintype "passive"))
      (node (ref "P1") (pin "1") (pinfunction "1_1") (pintype "passive"))
      (node (ref "P10") (pin "1") (pinfunction "1_1") (pintype "passive"))
      (node (ref "P11") (pin "1") (pinfunction "1_1") (pintype "passive"))
      (node (ref "P2") (pin "1") (pinfunction "1_1") (pintype "passive"))
      (node (ref "P3") (pin "1") (pinfunction "1_1") (pintype "passive"))
      (node (ref "P8") (pin "1") (pinfunction "1_1") (pintype "passive"))
      (node (ref "P9") (pin "1") (pinfunction "1_1") (pintype "passive"))
      (node (ref "P9") (pin "2") (pinfunction "2_2") (pintype "passive"))
      (node (ref "R1") (pin "1") (pinfunction "1_1") (pintype "passive"))
      (node (ref "R10") (pin "2") (pinfunction "2_2") (pintype "passive"))
      (node (ref "R11") (pin "2") (pinfunction "2_2") (pintype "passive"))
      (node (ref "R7") (pin "1") (pinfunction "1_1") (pintype "passive"))
      (node (ref "R8") (pin "1") (pinfunction "1_1") (pintype "passive"))
      (node (ref "TF1") (pin "4") (pinfunction "VDD_4") (pintype "passive"))
      (node (ref "U1") (pin "5") (pinfunction "OUT_5") (pintype "passive"))
      (node (ref "U4") (pin "13") (pinfunction "VDDA_13") (pintype "power_in"))
      (node (ref "U4") (pin "19") (pinfunction "VDD_4_19") (pintype "power_in"))
      (node (ref "U4") (pin "32") (pinfunction "VDD_1_32") (pintype "power_in"))
      (node (ref "U4") (pin "48") (pinfunction "VDD_2_48") (pintype "power_in"))
      (node (ref "U4") (pin "64") (pinfunction "VDD_3_64") (pintype "power_in"))
      (node (ref "U5") (pin "1") (pinfunction "VDDIO_1") (pintype "passive"))
      (node (ref "U5") (pin "10") (pinfunction "VDD_10") (pintype "passive"))
      (node (ref "U5") (pin "5") (pinfunction "SDO/SA0_5") (pintype "passive"))
      (node (ref "U5") (pin "6") (pinfunction "CS_6") (pintype "passive"))
      (node (ref "U6") (pin "1") (pinfunction "VDD_1") (pintype "passive"))
      (node (ref "U6") (pin "6") (pinfunction "CS_6") (pintype "passive"))
      (node (ref "U7") (pin "10") (pinfunction "VDD_IO_10") (pintype "passive"))
      (node (ref "U7") (pin "2") (pinfunction "CS_XL_2") (pintype "passive"))
      (node (ref "U7") (pin "3") (pinfunction "CS_MAG_3") (pintype "passive"))
      (node (ref "U7") (pin "9") (pinfunction "VDD_9") (pintype "passive"))
      (node (ref "U8") (pin "1") (pinfunction "SDO/SA0_1") (pintype "passive"))
      (node (ref "U8") (pin "12") (pinfunction "CS_12") (pintype "passive"))
      (node (ref "U8") (pin "2") (pinfunction "SDx_2") (pintype "passive"))
      (node (ref "U8") (pin "3") (pinfunction "SCx_3") (pintype "passive"))
      (node (ref "U8") (pin "5") (pinfunction "VDDIO_5") (pintype "passive"))
      (node (ref "U8") (pin "8") (pinfunction "VDD_8") (pintype "passive"))
    )
    (net (code "47") (name "3V3RF") (class "Default")
      (node (ref "C10") (pin "1") (pinfunction "1_1") (pintype "passive"))
      (node (ref "C13") (pin "1") (pinfunction "1_1") (pintype "passive"))
      (node (ref "C41") (pin "1") (pinfunction "1_1") (pintype "passive"))
      (node (ref "C5") (pin "1") (pinfunction "1_1") (pintype "passive"))
      (node (ref "L1") (pin "2") (pinfunction "2_2") (pintype "passive"))
      (node (ref "U2") (pin "19") (pinfunction "VBAT2_19") (pintype "passive"))
      (node (ref "U2") (pin "24") (pinfunction "VBAT1_24") (pintype "passive"))
      (node (ref "U2") (pin "5") (pinfunction "VBAT3_5") (pintype "passive"))
    )
    (net (code "48") (name "5V") (class "Default")
      (node (ref "F1") (pin "2") (pinfunction "2_2") (pintype "passive"))
      (node (ref "P12") (pin "1") (pinfunction "1_1") (pintype "passive"))
      (node (ref "P4") (pin "1") (pinfunction "1_1") (pintype "passive"))
      (node (ref "P5") (pin "1") (pinfunction "1_1") (pintype "passive"))
      (node (ref "P5") (pin "2") (pinfunction "2_2") (pintype "passive"))
      (node (ref "P5") (pin "3") (pinfunction "3_3") (pintype "passive"))
      (node (ref "P5") (pin "4") (pinfunction "4_4") (pintype "passive"))
      (node (ref "P5") (pin "5") (pinfunction "5_5") (pintype "passive"))
      (node (ref "P5") (pin "6") (pinfunction "6_6") (pintype "passive"))
      (node (ref "P5") (pin "7") (pinfunction "7_7") (pintype "passive"))
      (node (ref "P5") (pin "8") (pinfunction "8_8") (pintype "passive"))
    )
    (net (code "49") (name "GND") (class "Default")
      (node (ref "C1") (pin "2") (pinfunction "2_2") (pintype "passive"))
      (node (ref "C10") (pin "2") (pinfunction "2_2") (pintype "passive"))
      (node (ref "C12") (pin "1") (pinfunction "1_1") (pintype "passive"))
      (node (ref "C13") (pin "2") (pinfunction "2_2") (pintype "passive"))
      (node (ref "C15") (pin "2") (pinfunction "2_2") (pintype "passive"))
      (node (ref "C17") (pin "2") (pinfunction "2_2") (pintype "passive"))
      (node (ref "C18") (pin "2") (pinfunction "2_2") (pintype "passive"))
      (node (ref "C19") (pin "1") (pinfunction "1_1") (pintype "passive"))
      (node (ref "C2") (pin "2") (pinfunction "2_2") (pintype "passive"))
      (node (ref "C20") (pin "2") (pinfunction "2_2") (pintype "passive"))
      (node (ref "C21") (pin "1") (pinfunction "1_1") (pintype "passive"))
      (node (ref "C23") (pin "2") (pinfunction "2_2") (pintype "passive"))
      (node (ref "C24") (pin "2") (pinfunction "2_2") (pintype "passive"))
      (node (ref "C25") (pin "1") (pinfunction "1_1") (pintype "passive"))
      (node (ref "C26") (pin "1") (pinfunction "1_1") (pintype "passive"))
      (node (ref "C27") (pin "2") (pinfunction "2_2") (pintype "passive"))
      (node (ref "C28") (pin "2") (pinfunction "2_2") (pintype "passive"))
      (node (ref "C29") (pin "1") (pinfunction "1_1") (pintype "passive"))
      (node (ref "C3") (pin "2") (pinfunction "2_2") (pintype "passive"))
      (node (ref "C30") (pin "2") (pinfunction "2_2") (pintype "passive"))
      (node (ref "C31") (pin "1") (pinfunction "1_1") (pintype "passive"))
      (node (ref "C32") (pin "1") (pinfunction "1_1") (pintype "passive"))
      (node (ref "C33") (pin "1") (pinfunction "1_1") (pintype "passive"))
      (node (ref "C34") (pin "2") (pinfunction "2_2") (pintype "passive"))
      (node (ref "C35") (pin "2") (pinfunction "2_2") (pintype "passive"))
      (node (ref "C36") (pin "2") (pinfunction "2_2") (pintype "passive"))
      (node (ref "C37") (pin "2") (pinfunction "2_2") (pintype "passive"))
      (node (ref "C38") (pin "2") (pinfunction "2_2") (pintype "passive"))
      (node (ref "C39") (pin "2") (pinfunction "2_2") (pintype "passive"))
      (node (ref "C4") (pin "2") (pinfunction "2_2") (pintype "passive"))
      (node (ref "C40") (pin "1") (pinfunction "1_1") (pintype "passive"))
      (node (ref "C41") (pin "2") (pinfunction "2_2") (pintype "passive"))
      (node (ref "C42") (pin "2") (pinfunction "2_2") (pintype "passive"))
      (node (ref "C5") (pin "2") (pinfunction "2_2") (pintype "passive"))
      (node (ref "C6") (pin "1") (pinfunction "1_1") (pintype "passive"))
      (node (ref "C7") (pin "1") (pinfunction "1_1") (pintype "passive"))
      (node (ref "C8") (pin "1") (pinfunction "1_1") (pintype "passive"))
      (node (ref "CN1") (pin "1") (pinfunction "GND_1") (pintype "passive"))
      (node (ref "CN1") (pin "2") (pinfunction "GND_2") (pintype "passive"))
      (node (ref "CON1") (pin "1") (pinfunction "GND_1") (pintype "passive"))
      (node (ref "CON1") (pin "N0") (pinfunction "G_N0") (pintype "passive"))
      (node (ref "CON1") (pin "N1") (pinfunction "G_N1") (pintype "passive"))
      (node (ref "D1") (pin "1") (pinfunction "K_1") (pintype "passive"))
      (node (ref "D2") (pin "1") (pinfunction "A_1") (pintype "passive"))
      (node (ref "L3") (pin "2") (pinfunction "2_2") (pintype "passive"))
      (node (ref "L5") (pin "1") (pinfunction "1_1") (pintype "passive"))
      (node (ref "P1") (pin "4") (pinfunction "4_4") (pintype "passive"))
      (node (ref "P10") (pin "6") (pinfunction "6_6") (pintype "passive"))
      (node (ref "P11") (pin "6") (pinfunction "6_6") (pintype "passive"))
      (node (ref "P12") (pin "2") (pinfunction "2_2") (pintype "passive"))
      (node (ref "P2") (pin "4") (pinfunction "4_4") (pintype "passive"))
      (node (ref "P3") (pin "4") (pinfunction "4_4") (pintype "passive"))
      (node (ref "P7") (pin "1") (pinfunction "1_1") (pintype "passive"))
      (node (ref "P7") (pin "2") (pinfunction "2_2") (pintype "passive"))
      (node (ref "P7") (pin "3") (pinfunction "3_3") (pintype "passive"))
      (node (ref "P7") (pin "4") (pinfunction "4_4") (pintype "passive"))
      (node (ref "P7") (pin "5") (pinfunction "5_5") (pintype "passive"))
      (node (ref "P7") (pin "6") (pinfunction "6_6") (pintype "passive"))
      (node (ref "P7") (pin "7") (pinfunction "7_7") (pintype "passive"))
      (node (ref "P7") (pin "8") (pinfunction "8_8") (pintype "passive"))
      (node (ref "P8") (pin "4") (pinfunction "4_4") (pintype "passive"))
      (node (ref "P9") (pin "5") (pinfunction "5_5") (pintype "passive"))
      (node (ref "P9") (pin "6") (pinfunction "6_6") (pintype "passive"))
      (node (ref "R12") (pin "2") (pinfunction "2_2") (pintype "passive"))
      (node (ref "R4") (pin "2") (pinfunction "2_2") (pintype "passive"))
      (node (ref "RESET") (pin "1") (pinfunction "1_1") (pintype "passive"))
      (node (ref "TF1") (pin "6") (pinfunction "VSS_6") (pintype "passive"))
      (node (ref "TF1") (pin "FG1") (pinfunction "FG1_FG1") (pintype "passive"))
      (node (ref "TF1") (pin "FG2") (pinfunction "FG2_FG2") (pintype "passive"))
      (node (ref "TF1") (pin "FG3") (pinfunction "FG3_FG3") (pintype "passive"))
      (node (ref "TF1") (pin "FG4") (pinfunction "FG4_FG4") (pintype "passive"))
      (node (ref "U1") (pin "2") (pinfunction "GND_2") (pintype "passive"))
      (node (ref "U2") (pin "10") (pinfunction "TEST6_10") (pintype "passive"))
      (node (ref "U2") (pin "11") (pinfunction "TEST7_11") (pintype "passive"))
      (node (ref "U2") (pin "27") (pinfunction "NO_SMPS_27") (pintype "passive"))
      (node (ref "U2") (pin "30") (pinfunction "TEST10_30") (pintype "passive"))
      (node (ref "U2") (pin "6") (pinfunction "TEST2_6") (pintype "passive"))
      (node (ref "U2") (pin "7") (pinfunction "TEST3_7") (pintype "passive"))
      (node (ref "U2") (pin "8") (pinfunction "TEST4_8") (pintype "passive"))
      (node (ref "U2") (pin "9") (pinfunction "TEST5_9") (pintype "passive"))
      (node (ref "U3") (pin "A2") (pinfunction "A2_A2") (pintype "passive"))
      (node (ref "U4") (pin "12") (pinfunction "VSSA_12") (pintype "power_in"))
      (node (ref "U4") (pin "18") (pinfunction "VSS_4_18") (pintype "power_in"))
      (node (ref "U4") (pin "31") (pinfunction "VSS_1_31") (pintype "power_in"))
      (node (ref "U4") (pin "47") (pinfunction "VSS_2_47") (pintype "power_in"))
      (node (ref "U4") (pin "63") (pinfunction "VSS_3_63") (pintype "power_in"))
      (node (ref "U5") (pin "3") (pinfunction "RES_3") (pintype "passive"))
      (node (ref "U5") (pin "8") (pinfunction "GND_8") (pintype "passive"))
      (node (ref "U5") (pin "9") (pinfunction "GND_9") (pintype "passive"))
      (node (ref "U6") (pin "5") (pinfunction "GND_5") (pintype "passive"))
      (node (ref "U7") (pin "6") (pinfunction "GND_6") (pintype "passive"))
      (node (ref "U7") (pin "8") (pinfunction "GND_8") (pintype "passive"))
      (node (ref "U8") (pin "6") (pinfunction "GND_6") (pintype "passive"))
      (node (ref "U8") (pin "7") (pinfunction "GND_7") (pintype "passive"))
      (node (ref "Y1") (pin "2") (pintype "passive"))
      (node (ref "Y1") (pin "4") (pintype "passive"))
      (node (ref "Y3") (pin "2") (pintype "passive"))
      (node (ref "Y3") (pin "4") (pintype "passive"))
    )
    (net (code "50") (name "Net-(C11-Pad2)") (class "Default")
      (node (ref "C11") (pin "2") (pinfunction "2_2") (pintype "passive"))
      (node (ref "C9") (pin "2") (pinfunction "2_2") (pintype "passive"))
      (node (ref "L3") (pin "1") (pinfunction "1_1") (pintype "passive"))
    )
    (net (code "51") (name "Net-(C14-Pad2)") (class "Default")
      (node (ref "C14") (pin "2") (pinfunction "2_2") (pintype "passive"))
      (node (ref "C22") (pin "2") (pinfunction "2_2") (pintype "passive"))
      (node (ref "C26") (pin "2") (pinfunction "2_2") (pintype "passive"))
      (node (ref "L4") (pin "1") (pinfunction "1_1") (pintype "passive"))
    )
    (net (code "52") (name "Net-(C16-Pad2)") (class "Default")
      (node (ref "C16") (pin "2") (pinfunction "2_2") (pintype "passive"))
      (node (ref "L5") (pin "2") (pinfunction "2_2") (pintype "passive"))
    )
    (net (code "53") (name "Net-(C22-Pad1)") (class "Default")
      (node (ref "C22") (pin "1") (pinfunction "1_1") (pintype "passive"))
      (node (ref "U3") (pin "A1") (pinfunction "A1_A1") (pintype "passive"))
    )
    (net (code "54") (name "Net-(CN1-SIG)") (class "Default")
      (node (ref "C14") (pin "1") (pinfunction "1_1") (pintype "passive"))
      (node (ref "CN1") (pin "3") (pinfunction "SIG_3") (pintype "passive"))
    )
    (net (code "55") (name "Net-(CON1-5V)") (class "Default")
      (node (ref "CON1") (pin "5") (pinfunction "5V_5") (pintype "passive"))
      (node (ref "P4") (pin "2") (pinfunction "2_2") (pintype "passive"))
    )
    (net (code "56") (name "Net-(CON1-D+)") (class "Default")
      (node (ref "CON1") (pin "3") (pinfunction "D+_3") (pintype "passive"))
      (node (ref "R11") (pin "1") (pinfunction "1_1") (pintype "passive"))
      (node (ref "R3") (pin "1") (pinfunction "1_1") (pintype "passive"))
    )
    (net (code "57") (name "Net-(CON1-D-)") (class "Default")
      (node (ref "CON1") (pin "4") (pinfunction "D-_4") (pintype "passive"))
      (node (ref "R2") (pin "1") (pinfunction "1_1") (pintype "passive"))
    )
    (net (code "58") (name "Net-(CON1-NC)") (class "Default")
      (node (ref "CON1") (pin "2") (pinfunction "NC_2") (pintype "passive"))
      (node (ref "R12") (pin "1") (pinfunction "1_1") (pintype "passive"))
    )
    (net (code "59") (name "Net-(D1-A)") (class "Default")
      (node (ref "D1") (pin "2") (pinfunction "A_2") (pintype "passive"))
      (node (ref "R1") (pin "2") (pinfunction "2_2") (pintype "passive"))
    )
    (net (code "60") (name "Net-(D2-K)") (class "Default")
      (node (ref "C7") (pin "2") (pinfunction "2_2") (pintype "passive"))
      (node (ref "D2") (pin "2") (pinfunction "K_2") (pintype "passive"))
      (node (ref "F1") (pin "1") (pinfunction "1_1") (pintype "passive"))
      (node (ref "U1") (pin "1") (pinfunction "Vin_1") (pintype "passive"))
      (node (ref "U1") (pin "3") (pinfunction "EN_3") (pintype "passive"))
    )
    (net (code "61") (name "Net-(D3-K)") (class "Default")
      (node (ref "D3") (pin "1") (pinfunction "K_1") (pintype "passive"))
      (node (ref "R9") (pin "2") (pinfunction "2_2") (pintype "passive"))
    )
    (net (code "62") (name "Net-(E1-A)") (class "Default")
      (node (ref "C40") (pin "2") (pinfunction "2_2") (pintype "passive"))
      (node (ref "E1") (pin "1") (pinfunction "A_1") (pintype "passive"))
      (node (ref "L4") (pin "2") (pinfunction "2_2") (pintype "passive"))
    )
    (net (code "63") (name "Net-(P9-Pad3)") (class "Default")
      (node (ref "P9") (pin "3") (pinfunction "3_3") (pintype "passive"))
      (node (ref "R5") (pin "2") (pinfunction "2_2") (pintype "passive"))
    )
    (net (code "64") (name "Net-(P9-Pad4)") (class "Default")
      (node (ref "P9") (pin "4") (pinfunction "4_4") (pintype "passive"))
      (node (ref "R6") (pin "1") (pinfunction "1_1") (pintype "passive"))
    )
    (net (code "65") (name "Net-(TP1-TP)") (class "Default")
      (node (ref "TP1") (pin "1") (pinfunction "TP_1") (pintype "passive"))
      (node (ref "U2") (pin "13") (pinfunction "TEST8_13") (pintype "passive"))
    )
    (net (code "66") (name "Net-(TP2-TP)") (class "Default")
      (node (ref "TP2") (pin "1") (pinfunction "TP_1") (pintype "passive"))
      (node (ref "U2") (pin "14") (pinfunction "TEST9_14") (pintype "passive"))
    )
    (net (code "67") (name "Net-(U1-BYP)") (class "Default")
      (node (ref "C8") (pin "2") (pinfunction "2_2") (pintype "passive"))
      (node (ref "U1") (pin "4") (pinfunction "BYP_4") (pintype "passive"))
    )
    (net (code "68") (name "Net-(U2-FXTAL0)") (class "Default")
      (node (ref "C16") (pin "1") (pinfunction "1_1") (pintype "passive"))
      (node (ref "U2") (pin "18") (pinfunction "FXTAL0_18") (pintype "passive"))
      (node (ref "Y1") (pin "3") (pintype "passive"))
    )
    (net (code "69") (name "Net-(U2-FXTAL1)") (class "Default")
      (node (ref "C15") (pin "1") (pinfunction "1_1") (pintype "passive"))
      (node (ref "U2") (pin "17") (pinfunction "FXTAL1_17") (pintype "passive"))
      (node (ref "Y1") (pin "1") (pintype "passive"))
    )
    (net (code "70") (name "Net-(U2-RF0)") (class "Default")
      (node (ref "U2") (pin "21") (pinfunction "RF0_21") (pintype "passive"))
      (node (ref "U3") (pin "B1") (pinfunction "B1_B1") (pintype "passive"))
    )
    (net (code "71") (name "Net-(U2-RF1)") (class "Default")
      (node (ref "U2") (pin "20") (pinfunction "RF1_20") (pintype "passive"))
      (node (ref "U3") (pin "B2") (pinfunction "B2_B2") (pintype "passive"))
    )
    (net (code "72") (name "Net-(U2-SMPSFILT1)") (class "Default")
      (node (ref "L2") (pin "1") (pinfunction "1_1") (pintype "passive"))
      (node (ref "U2") (pin "26") (pinfunction "SMPSFILT1_26") (pintype "passive"))
    )
    (net (code "73") (name "Net-(U2-SMPSFILT2)") (class "Default")
      (node (ref "C1") (pin "1") (pinfunction "1_1") (pintype "passive"))
      (node (ref "C4") (pin "1") (pinfunction "1_1") (pintype "passive"))
      (node (ref "L2") (pin "2") (pinfunction "2_2") (pintype "passive"))
      (node (ref "U2") (pin "28") (pinfunction "SMPSFILT2_28") (pintype "passive"))
    )
    (net (code "74") (name "Net-(U2-SXTAL0)") (class "Default")
      (node (ref "C9") (pin "1") (pinfunction "1_1") (pintype "passive"))
      (node (ref "U2") (pin "23") (pinfunction "SXTAL0_23") (pintype "passive"))
      (node (ref "Y2") (pin "1") (pinfunction "OSC1_1") (pintype "passive"))
    )
    (net (code "75") (name "Net-(U2-SXTAL1)") (class "Default")
      (node (ref "C11") (pin "1") (pinfunction "1_1") (pintype "passive"))
      (node (ref "U2") (pin "22") (pinfunction "SXTAL1_22") (pintype "passive"))
      (node (ref "Y2") (pin "2") (pinfunction "OSC2_2") (pintype "passive"))
    )
    (net (code "76") (name "Net-(U2-VDD1V2)") (class "Default")
      (node (ref "C2") (pin "1") (pinfunction "1_1") (pintype "passive"))
      (node (ref "C3") (pin "1") (pinfunction "1_1") (pintype "passive"))
      (node (ref "U2") (pin "29") (pinfunction "VDD1V2_29") (pintype "passive"))
    )
    (net (code "77") (name "Net-(U2-VDD1V8)") (class "Default")
      (node (ref "C17") (pin "1") (pinfunction "1_1") (pintype "passive"))
      (node (ref "C18") (pin "1") (pinfunction "1_1") (pintype "passive"))
      (node (ref "U2") (pin "12") (pinfunction "VDD1V8_12") (pintype "passive"))
    )
    (net (code "78") (name "Net-(U4-OSC_IN{slash}PD0)") (class "Default")
      (node (ref "C23") (pin "1") (pinfunction "1_1") (pintype "passive"))
      (node (ref "U4") (pin "5") (pinfunction "OSC_IN/PD0_5") (pintype "input"))
      (node (ref "Y3") (pin "3") (pintype "passive"))
    )
    (net (code "79") (name "Net-(U4-OSC_OUT{slash}PD1)") (class "Default")
      (node (ref "C24") (pin "1") (pinfunction "1_1") (pintype "passive"))
      (node (ref "U4") (pin "6") (pinfunction "OSC_OUT/PD1_6") (pintype "output"))
      (node (ref "Y3") (pin "1") (pintype "passive"))
    )
    (net (code "80") (name "Net-(U4-PB3{slash}JTDO)") (class "Default")
      (node (ref "R9") (pin "1") (pinfunction "1_1") (pintype "passive"))
      (node (ref "U4") (pin "55") (pinfunction "PB3/JTDO_55") (pintype "bidirectional"))
    )
    (net (code "81") (name "Net-(U4-PC14-OSC32_IN)") (class "Default")
      (node (ref "C29") (pin "2") (pinfunction "2_2") (pintype "passive"))
      (node (ref "U4") (pin "3") (pinfunction "PC14-OSC32_IN_3") (pintype "bidirectional"))
      (node (ref "Y4") (pin "2") (pinfunction "OSC2_2") (pintype "passive"))
    )
    (net (code "82") (name "Net-(U4-PC15-OSC32_OUT)") (class "Default")
      (node (ref "C31") (pin "2") (pinfunction "2_2") (pintype "passive"))
      (node (ref "U4") (pin "4") (pinfunction "PC15-OSC32_OUT_4") (pintype "bidirectional"))
      (node (ref "Y4") (pin "1") (pinfunction "OSC1_1") (pintype "passive"))
    )
    (net (code "83") (name "Net-(U4-VBAT)") (class "Default")
      (node (ref "C28") (pin "1") (pinfunction "1_1") (pintype "passive"))
      (node (ref "U4") (pin "1") (pinfunction "VBAT_1") (pintype "power_in"))
    )
    (net (code "84") (name "Net-(U4-VCAP)") (class "Default")
      (node (ref "C30") (pin "1") (pinfunction "1_1") (pintype "passive"))
      (node (ref "U4") (pin "30") (pinfunction "VCAP_30") (pintype "power_in"))
    )
    (net (code "85") (name "Net-(U7-C1)") (class "Default")
      (node (ref "C32") (pin "2") (pinfunction "2_2") (pintype "passive"))
      (node (ref "U7") (pin "5") (pinfunction "C1_5") (pintype "passive"))
    )
    (net (code "86") (name "unconnected-(TF1-SD-Pad9)") (class "Default")
      (node (ref "TF1") (pin "9") (pinfunction "SD_9") (pintype "passive+no_connect"))
    )
    (net (code "87") (name "unconnected-(U2-TEST1-Pad4)") (class "Default")
      (node (ref "U2") (pin "4") (pinfunction "TEST1_4") (pintype "passive+no_connect"))
    )
    (net (code "88") (name "unconnected-(U2-TEST11-Pad15)") (class "Default")
      (node (ref "U2") (pin "15") (pinfunction "TEST11_15") (pintype "passive+no_connect"))
    )
    (net (code "89") (name "unconnected-(U2-TEST12-Pad16)") (class "Default")
      (node (ref "U2") (pin "16") (pinfunction "TEST12_16") (pintype "passive+no_connect"))
    )
    (net (code "90") (name "unconnected-(U4-PA15{slash}JTDI-Pad50)") (class "Default")
      (node (ref "U4") (pin "50") (pinfunction "PA15/JTDI_50") (pintype "bidirectional+no_connect"))
    )
    (net (code "91") (name "unconnected-(U4-PB4{slash}JNTRST-Pad56)") (class "Default")
      (node (ref "U4") (pin "56") (pinfunction "PB4/JNTRST_56") (pintype "bidirectional+no_connect"))
    )
    (net (code "92") (name "unconnected-(U7-INT1_XL-Pad12)") (class "Default")
      (node (ref "U7") (pin "12") (pinfunction "INT1_XL_12") (pintype "passive+no_connect"))
    )
    (net (code "93") (name "unconnected-(U7-INT2_XL-Pad11)") (class "Default")
      (node (ref "U7") (pin "11") (pinfunction "INT2_XL_11") (pintype "passive+no_connect"))
    )
    (net (code "94") (name "unconnected-(U8-INT2-Pad9)") (class "Default")
      (node (ref "U8") (pin "9") (pinfunction "INT2_9") (pintype "passive+no_connect"))
    )
    (net (code "95") (name "unconnected-(U8-NC-Pad11)") (class "Default")
      (node (ref "U8") (pin "11") (pinfunction "NC_11") (pintype "passive+no_connect"))
    )
    (net (code "96") (name "unconnected-(U8-OCS-Pad10)") (class "Default")
      (node (ref "U8") (pin "10") (pinfunction "OCS_10") (pintype "passive+no_connect"))
    )
  )
)
